# APP_1_PLL_m.net
KiCad netlist of a schematic drawn in Altium Designer
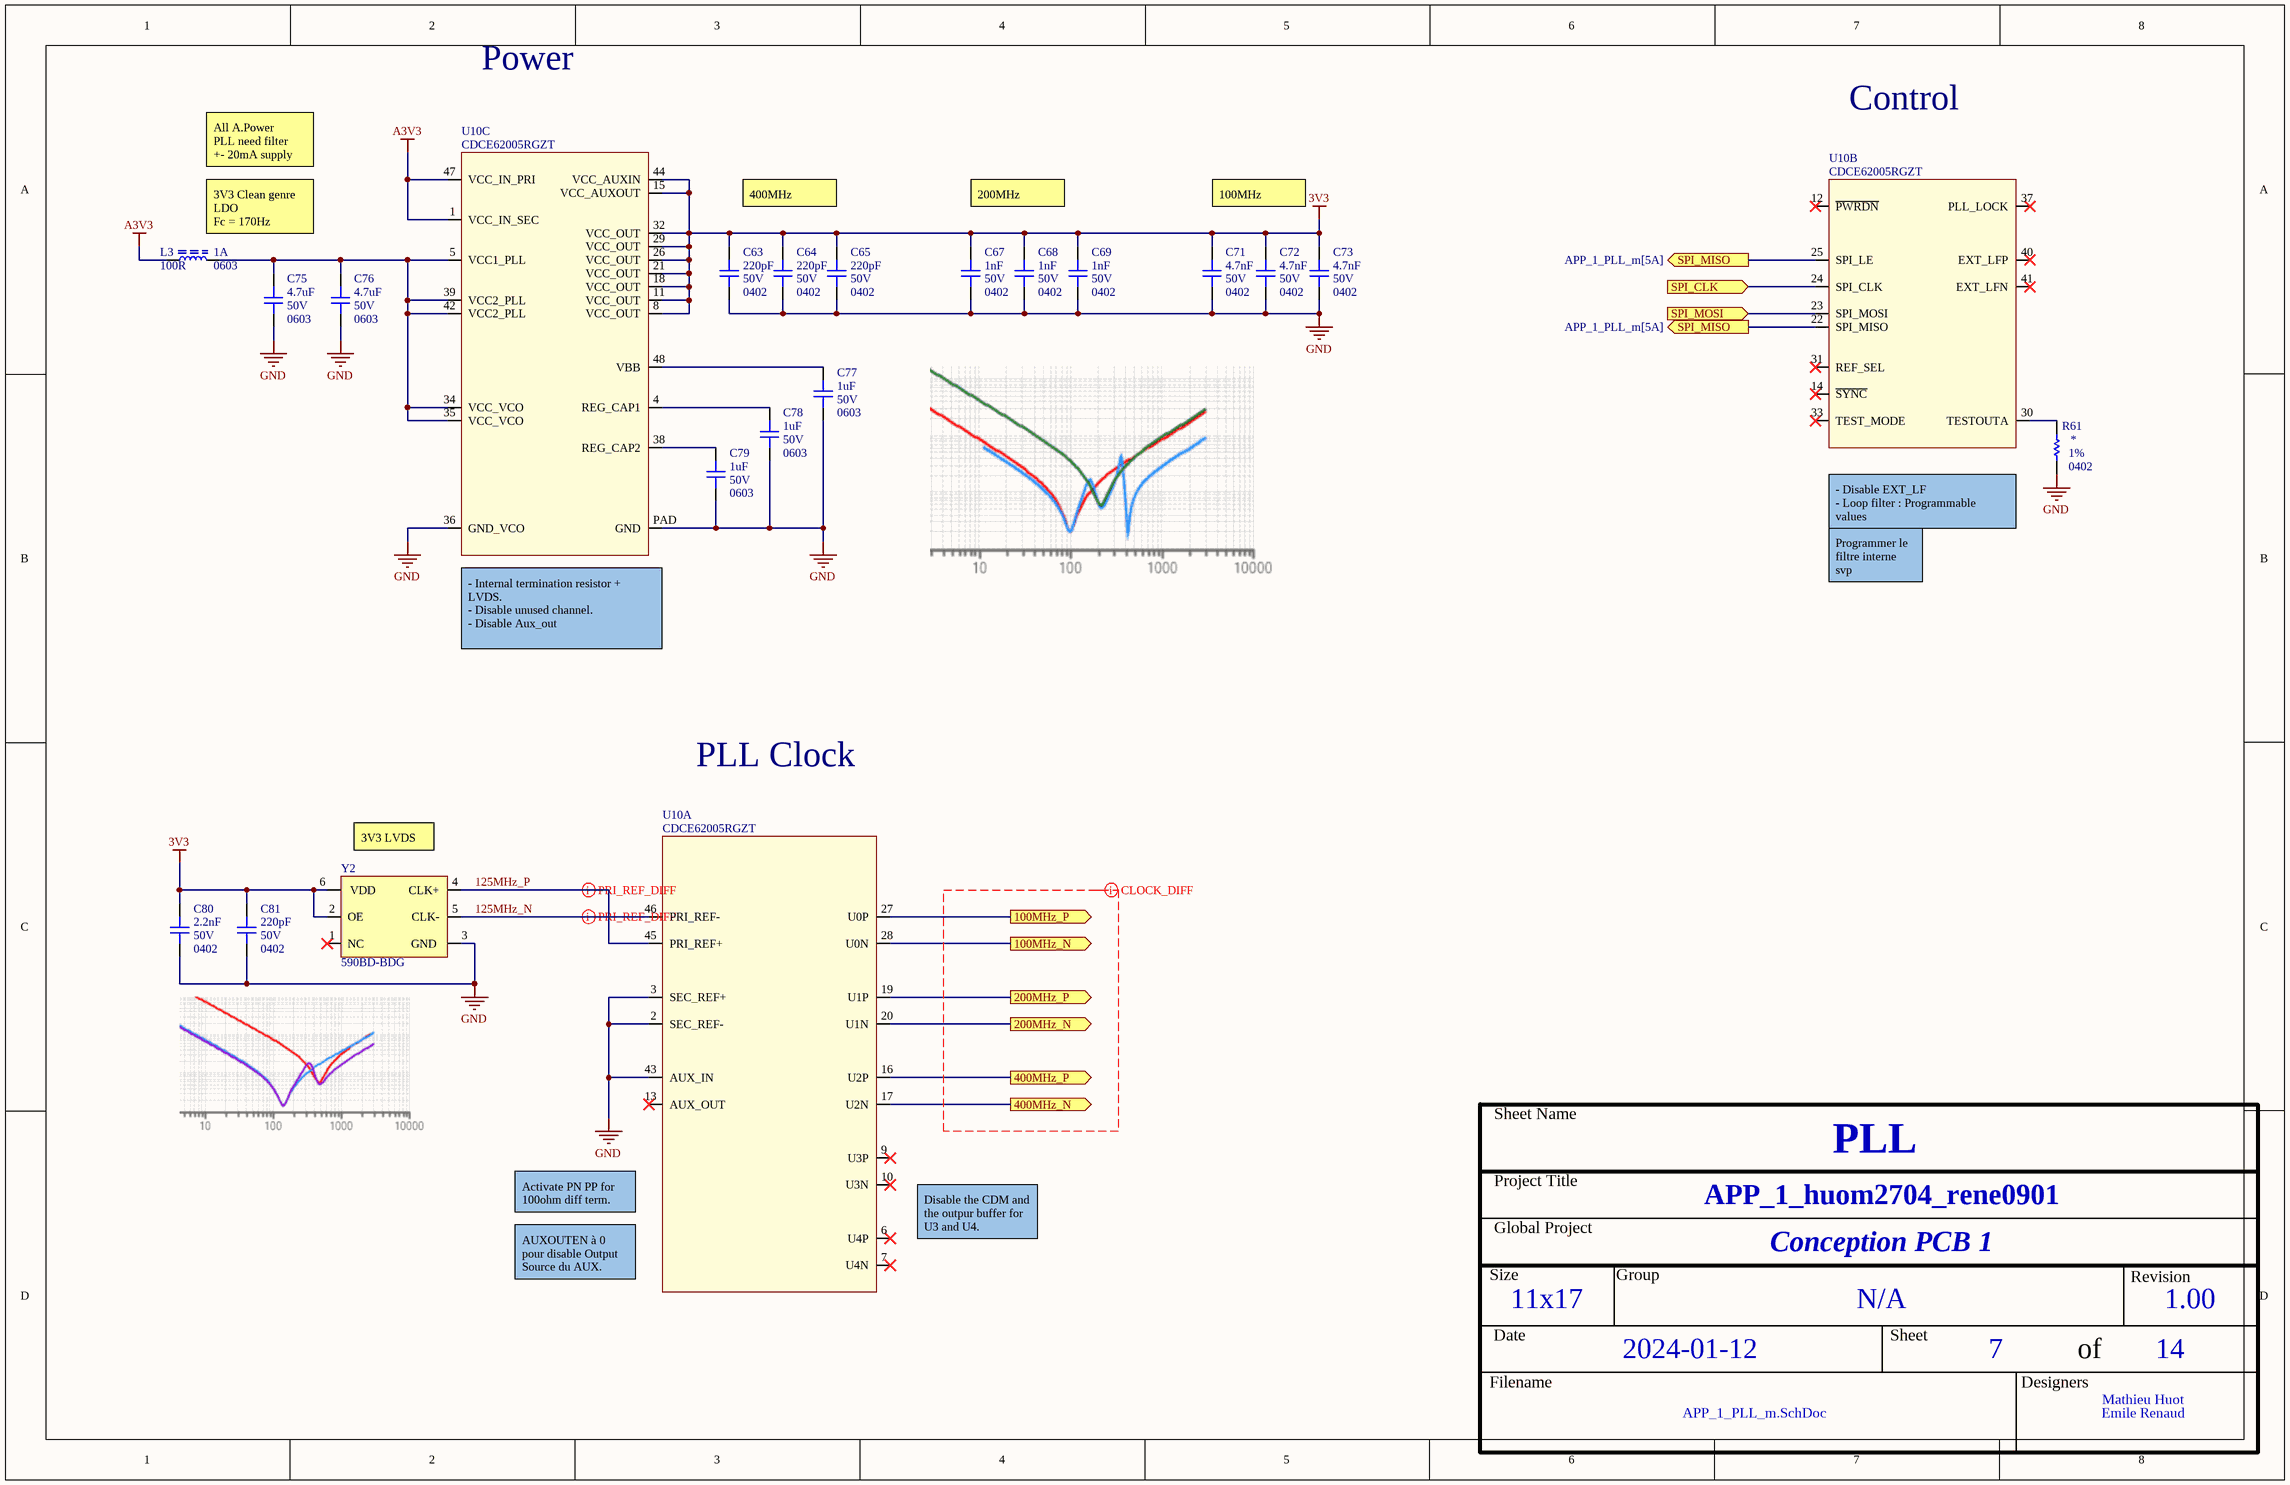
[diagram p0: APP_1_PLL_m.SchDoc]

(export (version "E")
  (design (tool "Eeschema 10.0.6"))
  (components
    (comp (ref "C63")
      (value "220pF")
      (footprint "CAP_0402")
      (description "CAP - 0402")
      (fields
        (field (name "VOLTAGE") "50V")
        (field (name "PACKAGE") "0402")
        (field (name "CREATEDBY") "Jonathan Bouchard")
      )
      (libsource (lib "S7CAS_LIB2023") (part "CAP - 0402"))
    )
    (comp (ref "C64")
      (value "220pF")
      (footprint "CAP_0402")
      (description "CAP - 0402")
      (fields
        (field (name "VOLTAGE") "50V")
        (field (name "PACKAGE") "0402")
        (field (name "CREATEDBY") "Jonathan Bouchard")
      )
      (libsource (lib "S7CAS_LIB2023") (part "CAP - 0402"))
    )
    (comp (ref "C65")
      (value "220pF")
      (footprint "CAP_0402")
      (description "CAP - 0402")
      (fields
        (field (name "VOLTAGE") "50V")
        (field (name "PACKAGE") "0402")
        (field (name "CREATEDBY") "Jonathan Bouchard")
      )
      (libsource (lib "S7CAS_LIB2023") (part "CAP - 0402"))
    )
    (comp (ref "C67")
      (value "1nF")
      (footprint "CAP_0402")
      (description "CAP - 0402")
      (fields
        (field (name "VOLTAGE") "50V")
        (field (name "PACKAGE") "0402")
        (field (name "CREATEDBY") "Jonathan Bouchard")
      )
      (libsource (lib "S7CAS_LIB2023") (part "CAP - 0402"))
    )
    (comp (ref "C68")
      (value "1nF")
      (footprint "CAP_0402")
      (description "CAP - 0402")
      (fields
        (field (name "VOLTAGE") "50V")
        (field (name "PACKAGE") "0402")
        (field (name "CREATEDBY") "Jonathan Bouchard")
      )
      (libsource (lib "S7CAS_LIB2023") (part "CAP - 0402"))
    )
    (comp (ref "C69")
      (value "1nF")
      (footprint "CAP_0402")
      (description "CAP - 0402")
      (fields
        (field (name "VOLTAGE") "50V")
        (field (name "PACKAGE") "0402")
        (field (name "CREATEDBY") "Jonathan Bouchard")
      )
      (libsource (lib "S7CAS_LIB2023") (part "CAP - 0402"))
    )
    (comp (ref "C71")
      (value "4.7nF")
      (footprint "CAP_0402")
      (description "CAP - 0402")
      (fields
        (field (name "VOLTAGE") "50V")
        (field (name "PACKAGE") "0402")
        (field (name "CREATEDBY") "Jonathan Bouchard")
      )
      (libsource (lib "S7CAS_LIB2023") (part "CAP - 0402"))
    )
    (comp (ref "C72")
      (value "4.7nF")
      (footprint "CAP_0402")
      (description "CAP - 0402")
      (fields
        (field (name "VOLTAGE") "50V")
        (field (name "PACKAGE") "0402")
        (field (name "CREATEDBY") "Jonathan Bouchard")
      )
      (libsource (lib "S7CAS_LIB2023") (part "CAP - 0402"))
    )
    (comp (ref "C73")
      (value "4.7nF")
      (footprint "CAP_0402")
      (description "CAP - 0402")
      (fields
        (field (name "VOLTAGE") "50V")
        (field (name "PACKAGE") "0402")
        (field (name "CREATEDBY") "Jonathan Bouchard")
      )
      (libsource (lib "S7CAS_LIB2023") (part "CAP - 0402"))
    )
    (comp (ref "C75")
      (value "4.7uF")
      (footprint "CAP_0603")
      (description "CAP - 0603")
      (fields
        (field (name "VOLTAGE") "50V")
        (field (name "PACKAGE") "0603")
        (field (name "CREATEDBY") "Jonathan Bouchard")
      )
      (libsource (lib "S7CAS_LIB2023") (part "CAP - 0603"))
    )
    (comp (ref "C76")
      (value "4.7uF")
      (footprint "CAP_0603")
      (description "CAP - 0603")
      (fields
        (field (name "VOLTAGE") "50V")
        (field (name "PACKAGE") "0603")
        (field (name "CREATEDBY") "Jonathan Bouchard")
      )
      (libsource (lib "S7CAS_LIB2023") (part "CAP - 0603"))
    )
    (comp (ref "C77")
      (value "1uF")
      (footprint "CAP_0603")
      (description "CAP - 0603")
      (fields
        (field (name "VOLTAGE") "50V")
        (field (name "PACKAGE") "0603")
        (field (name "CREATEDBY") "Jonathan Bouchard")
      )
      (libsource (lib "S7CAS_LIB2023") (part "CAP - 0603"))
    )
    (comp (ref "C78")
      (value "1uF")
      (footprint "CAP_0603")
      (description "CAP - 0603")
      (fields
        (field (name "VOLTAGE") "50V")
        (field (name "PACKAGE") "0603")
        (field (name "CREATEDBY") "Jonathan Bouchard")
      )
      (libsource (lib "S7CAS_LIB2023") (part "CAP - 0603"))
    )
    (comp (ref "C79")
      (value "1uF")
      (footprint "CAP_0603")
      (description "CAP - 0603")
      (fields
        (field (name "VOLTAGE") "50V")
        (field (name "PACKAGE") "0603")
        (field (name "CREATEDBY") "Jonathan Bouchard")
      )
      (libsource (lib "S7CAS_LIB2023") (part "CAP - 0603"))
    )
    (comp (ref "C80")
      (value "2.2nF")
      (footprint "CAP_0402")
      (description "CAP - 0402")
      (fields
        (field (name "VOLTAGE") "50V")
        (field (name "PACKAGE") "0402")
        (field (name "CREATEDBY") "Jonathan Bouchard")
      )
      (libsource (lib "S7CAS_LIB2023") (part "CAP - 0402"))
    )
    (comp (ref "C81")
      (value "220pF")
      (footprint "CAP_0402")
      (description "CAP - 0402")
      (fields
        (field (name "VOLTAGE") "50V")
        (field (name "PACKAGE") "0402")
        (field (name "CREATEDBY") "Jonathan Bouchard")
      )
      (libsource (lib "S7CAS_LIB2023") (part "CAP - 0402"))
    )
    (comp (ref "L3")
      (value "100R")
      (footprint "FER_0603")
      (description "FER - 0603")
      (fields
        (field (name "CURRENT") "1A")
        (field (name "PACKAGE") "0603")
        (field (name "CREATEDBY") "Jonathan Bouchard")
      )
      (libsource (lib "S7CAS_LIB2023") (part "FER - 0603"))
    )
    (comp (ref "R61")
      (value "RES - 0402")
      (footprint "RES_0402")
      (fields
        (field (name "VOLTAGE") "50V")
        (field (name "POWER") "1/16W")
        (field (name "PACKAGE") "0402")
        (field (name "PRECISION") "1%")
        (field (name "ALTIUM_VALUE") "*")
        (field (name "CREATEDBY") "Jonathan Bouchard")
      )
      (libsource (lib "S7CAS_LIB2023") (part "RES - 0402"))
    )
    (comp (ref "U10")
      (value "CDCE62005RGZT")
      (footprint "TIM_CDCE62005RGZT")
      (description "TIM - CLK SYNTH JITTER CLEANER 3:5 - QFN-48")
      (fields
        (field (name "VOLTAGE") "3 V ~ 3.6 V")
        (field (name "MFG") "Texas Instruments")
        (field (name "CREATEDBY") "Jonathan Bouchard")
      )
      (libsource (lib "S7CAS_LIB2023") (part "TIM_CDCE62005RGZT"))
    )
    (comp (ref "Y2")
      (value "590BD-BDG")
      (footprint "OSC_590BD-BDG")
      (description "TIM - OSC PROG 125MHz ~ 214.999MHz LVDS 3.3V 7PPM EN/DS - 6-SMD")
      (fields
        (field (name "CREATEDBY/DATE") "from 590BD-CDG")
        (field (name "VERIFIEDBY") "Caroline Paulin / 3/10/2019")
      )
      (libsource (lib "S7CAS_LIB2023") (part "OSC_590BD-BDG"))
    )
  )
  (nets
    (net (code "1") (name "/100MHz_N") (class "Default")
      (node (ref "U10") (pin "28") (pinfunction "U0N_28") (pintype "passive"))
    )
    (net (code "2") (name "/100MHz_P") (class "Default")
      (node (ref "U10") (pin "27") (pinfunction "U0P_27") (pintype "passive"))
    )
    (net (code "3") (name "/125MHz_N") (class "Default")
      (node (ref "U10") (pin "46") (pinfunction "PRI_REF-_46") (pintype "passive"))
      (node (ref "Y2") (pin "5") (pinfunction "CLK-_5") (pintype "passive"))
    )
    (net (code "4") (name "/125MHz_P") (class "Default")
      (node (ref "U10") (pin "45") (pinfunction "PRI_REF+_45") (pintype "passive"))
      (node (ref "Y2") (pin "4") (pinfunction "CLK+_4") (pintype "passive"))
    )
    (net (code "5") (name "/200MHz_N") (class "Default")
      (node (ref "U10") (pin "20") (pinfunction "U1N_20") (pintype "passive"))
    )
    (net (code "6") (name "/200MHz_P") (class "Default")
      (node (ref "U10") (pin "19") (pinfunction "U1P_19") (pintype "passive"))
    )
    (net (code "7") (name "/400MHz_N") (class "Default")
      (node (ref "U10") (pin "17") (pinfunction "U2N_17") (pintype "passive"))
    )
    (net (code "8") (name "/400MHz_P") (class "Default")
      (node (ref "U10") (pin "16") (pinfunction "U2P_16") (pintype "passive"))
    )
    (net (code "9") (name "/SPI_CLK") (class "Default")
      (node (ref "U10") (pin "24") (pinfunction "SPI_CLK_24") (pintype "passive"))
    )
    (net (code "10") (name "/SPI_MISO") (class "Default")
      (node (ref "U10") (pin "22") (pinfunction "SPI_MISO_22") (pintype "passive"))
      (node (ref "U10") (pin "25") (pinfunction "SPI_LE_25") (pintype "passive"))
    )
    (net (code "11") (name "/SPI_MOSI") (class "Default")
      (node (ref "U10") (pin "23") (pinfunction "SPI_MOSI_23") (pintype "passive"))
    )
    (net (code "12") (name "3V3") (class "Default")
      (node (ref "C63") (pin "2") (pinfunction "2_2") (pintype "passive"))
      (node (ref "C64") (pin "2") (pinfunction "2_2") (pintype "passive"))
      (node (ref "C65") (pin "2") (pinfunction "2_2") (pintype "passive"))
      (node (ref "C67") (pin "2") (pinfunction "2_2") (pintype "passive"))
      (node (ref "C68") (pin "2") (pinfunction "2_2") (pintype "passive"))
      (node (ref "C69") (pin "2") (pinfunction "2_2") (pintype "passive"))
      (node (ref "C71") (pin "2") (pinfunction "2_2") (pintype "passive"))
      (node (ref "C72") (pin "2") (pinfunction "2_2") (pintype "passive"))
      (node (ref "C73") (pin "2") (pinfunction "2_2") (pintype "passive"))
      (node (ref "C80") (pin "2") (pinfunction "2_2") (pintype "passive"))
      (node (ref "C81") (pin "2") (pinfunction "2_2") (pintype "passive"))
      (node (ref "U10") (pin "11") (pinfunction "VCC_OUT_11") (pintype "passive"))
      (node (ref "U10") (pin "15") (pinfunction "VCC_AUXOUT_15") (pintype "passive"))
      (node (ref "U10") (pin "18") (pinfunction "VCC_OUT_18") (pintype "passive"))
      (node (ref "U10") (pin "21") (pinfunction "VCC_OUT_21") (pintype "passive"))
      (node (ref "U10") (pin "26") (pinfunction "VCC_OUT_26") (pintype "passive"))
      (node (ref "U10") (pin "29") (pinfunction "VCC_OUT_29") (pintype "passive"))
      (node (ref "U10") (pin "32") (pinfunction "VCC_OUT_32") (pintype "passive"))
      (node (ref "U10") (pin "44") (pinfunction "VCC_AUXIN_44") (pintype "passive"))
      (node (ref "U10") (pin "8") (pinfunction "VCC_OUT_8") (pintype "passive"))
      (node (ref "Y2") (pin "2") (pinfunction "OE_2") (pintype "passive"))
      (node (ref "Y2") (pin "6") (pinfunction "VDD_6") (pintype "passive"))
    )
    (net (code "13") (name "A3V3") (class "Default")
      (node (ref "L3") (pin "2") (pinfunction "2_2") (pintype "passive"))
      (node (ref "U10") (pin "1") (pinfunction "VCC_IN_SEC_1") (pintype "passive"))
      (node (ref "U10") (pin "47") (pinfunction "VCC_IN_PRI_47") (pintype "passive"))
    )
    (net (code "14") (name "GND") (class "Default")
      (node (ref "C63") (pin "1") (pinfunction "1_1") (pintype "passive"))
      (node (ref "C64") (pin "1") (pinfunction "1_1") (pintype "passive"))
      (node (ref "C65") (pin "1") (pinfunction "1_1") (pintype "passive"))
      (node (ref "C67") (pin "1") (pinfunction "1_1") (pintype "passive"))
      (node (ref "C68") (pin "1") (pinfunction "1_1") (pintype "passive"))
      (node (ref "C69") (pin "1") (pinfunction "1_1") (pintype "passive"))
      (node (ref "C71") (pin "1") (pinfunction "1_1") (pintype "passive"))
      (node (ref "C72") (pin "1") (pinfunction "1_1") (pintype "passive"))
      (node (ref "C73") (pin "1") (pinfunction "1_1") (pintype "passive"))
      (node (ref "C75") (pin "1") (pinfunction "1_1") (pintype "passive"))
      (node (ref "C76") (pin "1") (pinfunction "1_1") (pintype "passive"))
      (node (ref "C77") (pin "1") (pinfunction "1_1") (pintype "passive"))
      (node (ref "C78") (pin "1") (pinfunction "1_1") (pintype "passive"))
      (node (ref "C79") (pin "1") (pinfunction "1_1") (pintype "passive"))
      (node (ref "C80") (pin "1") (pinfunction "1_1") (pintype "passive"))
      (node (ref "C81") (pin "1") (pinfunction "1_1") (pintype "passive"))
      (node (ref "R61") (pin "1") (pinfunction "1_1") (pintype "passive"))
      (node (ref "U10") (pin "2") (pinfunction "SEC_REF-_2") (pintype "passive"))
      (node (ref "U10") (pin "3") (pinfunction "SEC_REF+_3") (pintype "passive"))
      (node (ref "U10") (pin "36") (pinfunction "GND_VCO_36") (pintype "passive"))
      (node (ref "U10") (pin "43") (pinfunction "AUX_IN_43") (pintype "passive"))
      (node (ref "U10") (pin "PAD") (pinfunction "GND_PAD") (pintype "passive"))
      (node (ref "Y2") (pin "3") (pinfunction "GND_3") (pintype "passive"))
    )
    (net (code "15") (name "Net-(U10B-TESTOUTA)") (class "Default")
      (node (ref "R61") (pin "2") (pinfunction "2_2") (pintype "passive"))
      (node (ref "U10") (pin "30") (pinfunction "TESTOUTA_30") (pintype "passive"))
    )
    (net (code "16") (name "Net-(U10C-REG_CAP1)") (class "Default")
      (node (ref "C78") (pin "2") (pinfunction "2_2") (pintype "passive"))
      (node (ref "U10") (pin "4") (pinfunction "REG_CAP1_4") (pintype "passive"))
    )
    (net (code "17") (name "Net-(U10C-REG_CAP2)") (class "Default")
      (node (ref "C79") (pin "2") (pinfunction "2_2") (pintype "passive"))
      (node (ref "U10") (pin "38") (pinfunction "REG_CAP2_38") (pintype "passive"))
    )
    (net (code "18") (name "Net-(U10C-VBB)") (class "Default")
      (node (ref "C77") (pin "2") (pinfunction "2_2") (pintype "passive"))
      (node (ref "U10") (pin "48") (pinfunction "VBB_48") (pintype "passive"))
    )
    (net (code "19") (name "Net-(U10C-VCC1_PLL)") (class "Default")
      (node (ref "C75") (pin "2") (pinfunction "2_2") (pintype "passive"))
      (node (ref "C76") (pin "2") (pinfunction "2_2") (pintype "passive"))
      (node (ref "L3") (pin "1") (pinfunction "1_1") (pintype "passive"))
      (node (ref "U10") (pin "34") (pinfunction "VCC_VCO_34") (pintype "passive"))
      (node (ref "U10") (pin "35") (pinfunction "VCC_VCO_35") (pintype "passive"))
      (node (ref "U10") (pin "39") (pinfunction "VCC2_PLL_39") (pintype "passive"))
      (node (ref "U10") (pin "42") (pinfunction "VCC2_PLL_42") (pintype "passive"))
      (node (ref "U10") (pin "5") (pinfunction "VCC1_PLL_5") (pintype "passive"))
    )
    (net (code "20") (name "unconnected-(U10A-AUX_OUT-Pad13)") (class "Default")
      (node (ref "U10") (pin "13") (pinfunction "AUX_OUT_13") (pintype "passive+no_connect"))
    )
    (net (code "21") (name "unconnected-(U10A-U3N-Pad10)") (class "Default")
      (node (ref "U10") (pin "10") (pinfunction "U3N_10") (pintype "passive+no_connect"))
    )
    (net (code "22") (name "unconnected-(U10A-U3P-Pad9)") (class "Default")
      (node (ref "U10") (pin "9") (pinfunction "U3P_9") (pintype "passive+no_connect"))
    )
    (net (code "23") (name "unconnected-(U10A-U4N-Pad7)") (class "Default")
      (node (ref "U10") (pin "7") (pinfunction "U4N_7") (pintype "passive+no_connect"))
    )
    (net (code "24") (name "unconnected-(U10A-U4P-Pad6)") (class "Default")
      (node (ref "U10") (pin "6") (pinfunction "U4P_6") (pintype "passive+no_connect"))
    )
    (net (code "25") (name "unconnected-(U10B-EXT_LFN-Pad41)") (class "Default")
      (node (ref "U10") (pin "41") (pinfunction "EXT_LFN_41") (pintype "passive+no_connect"))
    )
    (net (code "26") (name "unconnected-(U10B-EXT_LFP-Pad40)") (class "Default")
      (node (ref "U10") (pin "40") (pinfunction "EXT_LFP_40") (pintype "passive+no_connect"))
    )
    (net (code "27") (name "unconnected-(U10B-PLL_LOCK-Pad37)") (class "Default")
      (node (ref "U10") (pin "37") (pinfunction "PLL_LOCK_37") (pintype "passive+no_connect"))
    )
    (net (code "28") (name "unconnected-(U10B-REF_SEL-Pad31)") (class "Default")
      (node (ref "U10") (pin "31") (pinfunction "REF_SEL_31") (pintype "passive+no_connect"))
    )
    (net (code "29") (name "unconnected-(U10B-TEST_MODE-Pad33)") (class "Default")
      (node (ref "U10") (pin "33") (pinfunction "TEST_MODE_33") (pintype "passive+no_connect"))
    )
    (net (code "30") (name "unconnected-(U10B-~{PWRDN}-Pad12)") (class "Default")
      (node (ref "U10") (pin "12") (pinfunction "~{PWRDN}_12") (pintype "passive+no_connect"))
    )
    (net (code "31") (name "unconnected-(U10B-~{SYNC}-Pad14)") (class "Default")
      (node (ref "U10") (pin "14") (pinfunction "~{SYNC}_14") (pintype "passive+no_connect"))
    )
    (net (code "32") (name "unconnected-(Y2-NC-Pad1)") (class "Default")
      (node (ref "Y2") (pin "1") (pinfunction "NC_1") (pintype "passive+no_connect"))
    )
  )
)
